# ICS40300-Silicon-Mic_Rev-A1.net
KiCad netlist of a schematic drawn in EAGLE
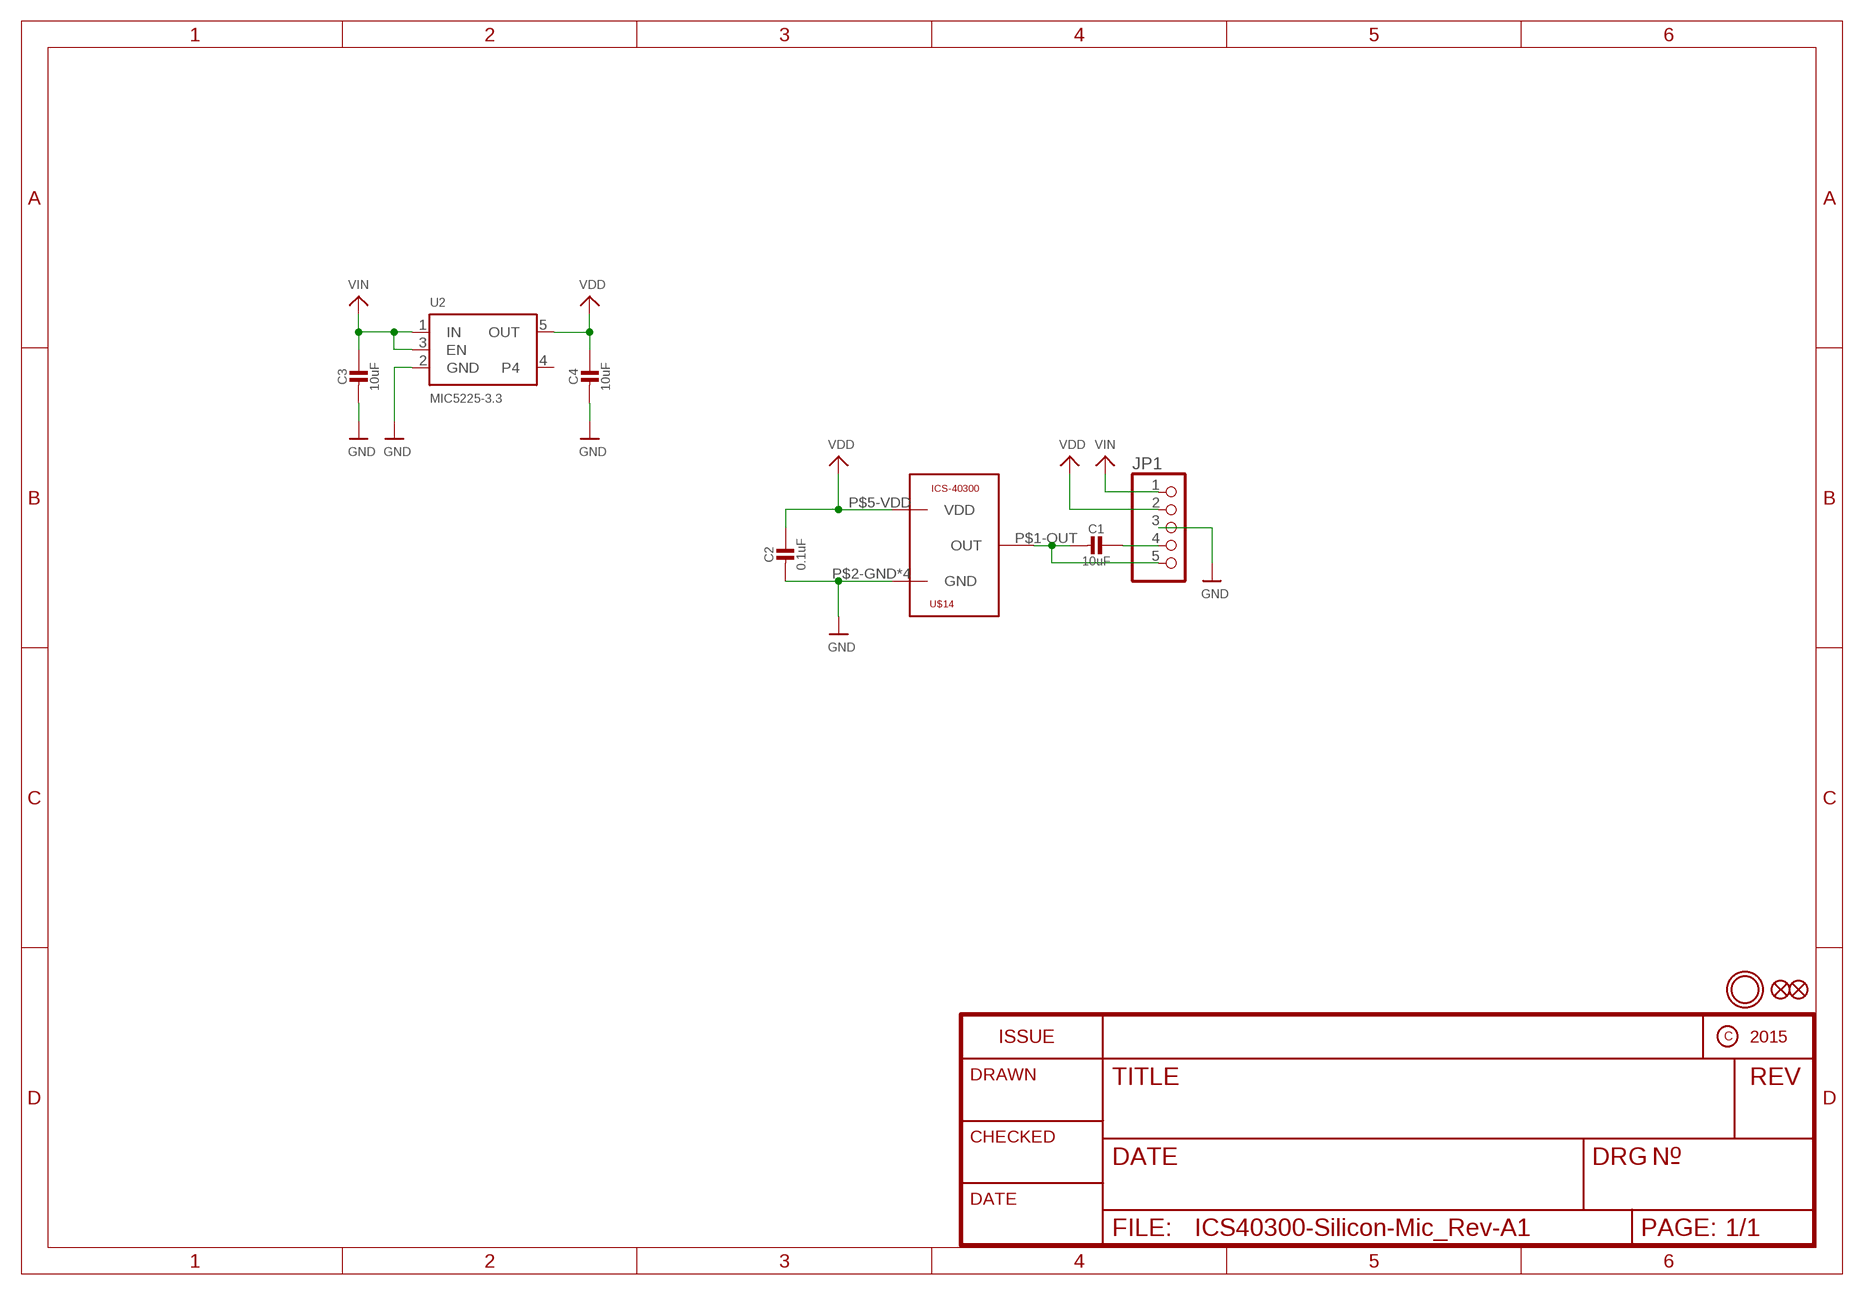
[diagram p0: schematic, sheet 1]

(export (version "E")
  (design (tool "Eeschema 10.0.6"))
  (components
    (comp (ref "C1")
      (value "10uF")
      (footprint "eagle-import:0805-NO")
      (libsource (lib "eagle-import") (part "CAP_CERAMIC0805-NOOUTLINE"))
    )
    (comp (ref "C2")
      (value "0.1uF")
      (footprint "eagle-import:0805-NO")
      (libsource (lib "eagle-import") (part "CAP_CERAMIC0805-NOOUTLINE"))
    )
    (comp (ref "C3")
      (value "10uF")
      (footprint "eagle-import:0805-NO")
      (libsource (lib "eagle-import") (part "CAP_CERAMIC0805-NOOUTLINE"))
    )
    (comp (ref "C4")
      (value "10uF")
      (footprint "eagle-import:0805-NO")
      (libsource (lib "eagle-import") (part "CAP_CERAMIC0805-NOOUTLINE"))
    )
    (comp (ref "FID1")
      (value "FIDUCIAL\"\"")
      (footprint "eagle-import:FIDUCIAL_1MM")
      (libsource (lib "eagle-import") (part "FIDUCIAL{dblquote}{dblquote}"))
    )
    (comp (ref "FID2")
      (value "FIDUCIAL\"\"")
      (footprint "eagle-import:FIDUCIAL_1MM")
      (libsource (lib "eagle-import") (part "FIDUCIAL{dblquote}{dblquote}"))
    )
    (comp (ref "JP1")
      (value "HEADER-1X576MIL")
      (footprint "eagle-import:1X05_ROUND_76")
      (libsource (lib "eagle-import") (part "HEADER-1X576MIL"))
    )
    (comp (ref "U$12")
      (value "MOUNTINGHOLE2.5")
      (footprint "eagle-import:MOUNTINGHOLE_2.5_PLATED")
      (libsource (lib "eagle-import") (part "MOUNTINGHOLE2.5"))
    )
    (comp (ref "U$14")
      (value "ICS-40300")
      (footprint "eagle-import:ICS-40300")
      (libsource (lib "eagle-import") (part "ICS-40300"))
    )
    (comp (ref "U2")
      (value "MIC5225-3.3")
      (footprint "eagle-import:SOT23-5")
      (libsource (lib "eagle-import") (part "VREG_SOT23-5"))
    )
  )
  (nets
    (net (code "1") (name "GND") (class "Default")
      (node (ref "C2") (pin "2") (pinfunction "2_2") (pintype "passive"))
      (node (ref "C3") (pin "2") (pinfunction "2_2") (pintype "passive"))
      (node (ref "C4") (pin "2") (pinfunction "2_2") (pintype "passive"))
      (node (ref "JP1") (pin "3") (pinfunction "3_3") (pintype "passive"))
      (node (ref "U$14") (pin "P$2-GND") (pinfunction "GND_P$2-GND") (pintype "bidirectional"))
      (node (ref "U$14") (pin "P$3-GND") (pinfunction "GND_P$3-GND") (pintype "bidirectional"))
      (node (ref "U$14") (pin "P$4-GND") (pinfunction "GND_P$4-GND") (pintype "bidirectional"))
      (node (ref "U$14") (pin "P$6-GND") (pinfunction "GND_P$6-GND") (pintype "bidirectional"))
      (node (ref "U2") (pin "2") (pinfunction "GND_2") (pintype "power_in"))
    )
    (net (code "2") (name "Net-(C1-Pad1)") (class "Default")
      (node (ref "C1") (pin "1") (pinfunction "1_1") (pintype "passive"))
      (node (ref "JP1") (pin "4") (pinfunction "4_4") (pintype "passive"))
    )
    (net (code "3") (name "Net-(U$14-OUT)") (class "Default")
      (node (ref "C1") (pin "2") (pinfunction "2_2") (pintype "passive"))
      (node (ref "JP1") (pin "5") (pinfunction "5_5") (pintype "passive"))
      (node (ref "U$14") (pin "P$1-OUT") (pinfunction "OUT_P$1-OUT") (pintype "bidirectional"))
    )
    (net (code "4") (name "VDD") (class "Default")
      (node (ref "C2") (pin "1") (pinfunction "1_1") (pintype "passive"))
      (node (ref "C4") (pin "1") (pinfunction "1_1") (pintype "passive"))
      (node (ref "JP1") (pin "2") (pinfunction "2_2") (pintype "passive"))
      (node (ref "U$14") (pin "P$5-VDD") (pinfunction "VDD_P$5-VDD") (pintype "bidirectional"))
      (node (ref "U2") (pin "5") (pinfunction "OUT_5") (pintype "power_in"))
    )
    (net (code "5") (name "VIN") (class "Default")
      (node (ref "C3") (pin "1") (pinfunction "1_1") (pintype "passive"))
      (node (ref "JP1") (pin "1") (pinfunction "1_1") (pintype "passive"))
      (node (ref "U2") (pin "1") (pinfunction "IN_1") (pintype "power_in"))
      (node (ref "U2") (pin "3") (pinfunction "EN_3") (pintype "input"))
    )
    (net (code "6") (name "unconnected-(U2-P4-Pad4)") (class "Default")
      (node (ref "U2") (pin "4") (pinfunction "P4_4") (pintype "bidirectional"))
    )
  )
)
